# DUAL_POWER_SUPPLY.net
KiCad netlist of a schematic drawn in EAGLE
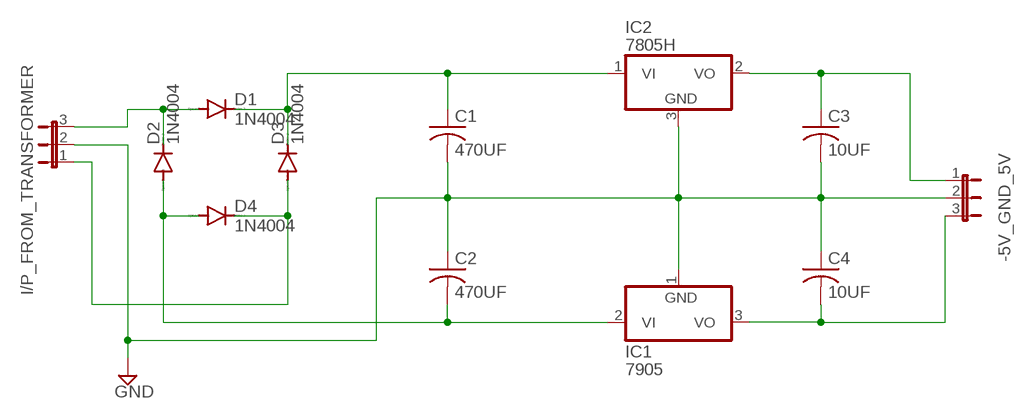
[diagram p0: schematic, sheet 1]

(export (version "E")
  (design (tool "Eeschema 10.0.6"))
  (components
    (comp (ref "-5V_GND_5V")
      (value "JP2W")
      (footprint "eagle-import:JP2W")
      (libsource (lib "eagle-import") (part "JP2W"))
    )
    (comp (ref "C1")
      (value "470UF")
      (footprint "eagle-import:C025-024X044")
      (libsource (lib "eagle-import") (part "C-US025-024X044"))
    )
    (comp (ref "C2")
      (value "470UF")
      (footprint "eagle-import:C025-024X044")
      (libsource (lib "eagle-import") (part "C-US025-024X044"))
    )
    (comp (ref "C3")
      (value "10UF")
      (footprint "eagle-import:C025-024X044")
      (libsource (lib "eagle-import") (part "C-US025-024X044"))
    )
    (comp (ref "C4")
      (value "10UF")
      (footprint "eagle-import:C025-024X044")
      (libsource (lib "eagle-import") (part "C-US025-024X044"))
    )
    (comp (ref "D1")
      (value "1N4004")
      (footprint "eagle-import:DO41-10")
      (libsource (lib "eagle-import") (part "1N4004"))
    )
    (comp (ref "D2")
      (value "1N4004")
      (footprint "eagle-import:DO41-10")
      (libsource (lib "eagle-import") (part "1N4004"))
    )
    (comp (ref "D3")
      (value "1N4004")
      (footprint "eagle-import:DO41-10")
      (libsource (lib "eagle-import") (part "1N4004"))
    )
    (comp (ref "D4")
      (value "1N4004")
      (footprint "eagle-import:DO41-10")
      (libsource (lib "eagle-import") (part "1N4004"))
    )
    (comp (ref "I/P_FROM_TRANSFORMER")
      (value "JP2W")
      (footprint "eagle-import:JP2W")
      (libsource (lib "eagle-import") (part "JP2W"))
    )
    (comp (ref "IC1")
      (value "7905")
      (footprint "eagle-import:TO39")
      (libsource (lib "eagle-import") (part "79H05"))
    )
    (comp (ref "IC2")
      (value "7805H")
      (footprint "eagle-import:TO39")
      (libsource (lib "eagle-import") (part "78H05"))
    )
  )
  (nets
    (net (code "1") (name "GND") (class "Default")
      (node (ref "-5V_GND_5V") (pin "2") (pinfunction "2_2") (pintype "passive"))
      (node (ref "C1") (pin "2") (pinfunction "2_2") (pintype "passive"))
      (node (ref "C2") (pin "1") (pinfunction "1_1") (pintype "passive"))
      (node (ref "C3") (pin "2") (pinfunction "2_2") (pintype "passive"))
      (node (ref "C4") (pin "1") (pinfunction "1_1") (pintype "passive"))
      (node (ref "I/P_FROM_TRANSFORMER") (pin "2") (pinfunction "2_2") (pintype "passive"))
      (node (ref "IC1") (pin "1") (pinfunction "GND_1") (pintype "passive"))
      (node (ref "IC2") (pin "3") (pinfunction "GND_3") (pintype "passive"))
    )
    (net (code "2") (name "Net-(D1-PadA)") (class "Default")
      (node (ref "D1") (pin "A") (pinfunction "A_A") (pintype "passive"))
      (node (ref "D2") (pin "C") (pinfunction "C_C") (pintype "passive"))
      (node (ref "I/P_FROM_TRANSFORMER") (pin "3") (pinfunction "3_3") (pintype "passive"))
    )
    (net (code "3") (name "Net-(D3-PadA)") (class "Default")
      (node (ref "D3") (pin "A") (pinfunction "A_A") (pintype "passive"))
      (node (ref "D4") (pin "C") (pinfunction "C_C") (pintype "passive"))
      (node (ref "I/P_FROM_TRANSFORMER") (pin "1") (pinfunction "1_1") (pintype "passive"))
    )
    (net (code "4") (name "Net-(IC1-VI)") (class "Default")
      (node (ref "C2") (pin "2") (pinfunction "2_2") (pintype "passive"))
      (node (ref "D2") (pin "A") (pinfunction "A_A") (pintype "passive"))
      (node (ref "D4") (pin "A") (pinfunction "A_A") (pintype "passive"))
      (node (ref "IC1") (pin "2") (pinfunction "VI_2") (pintype "input"))
    )
    (net (code "5") (name "Net-(IC1-VO)") (class "Default")
      (node (ref "-5V_GND_5V") (pin "3") (pinfunction "3_3") (pintype "passive"))
      (node (ref "C4") (pin "2") (pinfunction "2_2") (pintype "passive"))
      (node (ref "IC1") (pin "3") (pinfunction "VO_3") (pintype "passive"))
    )
    (net (code "6") (name "Net-(IC2-VI)") (class "Default")
      (node (ref "C1") (pin "1") (pinfunction "1_1") (pintype "passive"))
      (node (ref "D1") (pin "C") (pinfunction "C_C") (pintype "passive"))
      (node (ref "D3") (pin "C") (pinfunction "C_C") (pintype "passive"))
      (node (ref "IC2") (pin "1") (pinfunction "VI_1") (pintype "input"))
    )
    (net (code "7") (name "Net-(IC2-VO)") (class "Default")
      (node (ref "-5V_GND_5V") (pin "1") (pinfunction "1_1") (pintype "passive"))
      (node (ref "C3") (pin "1") (pinfunction "1_1") (pintype "passive"))
      (node (ref "IC2") (pin "2") (pinfunction "VO_2") (pintype "passive"))
    )
  )
)
